# Motion_2.net
KiCad netlist of a schematic drawn in EAGLE
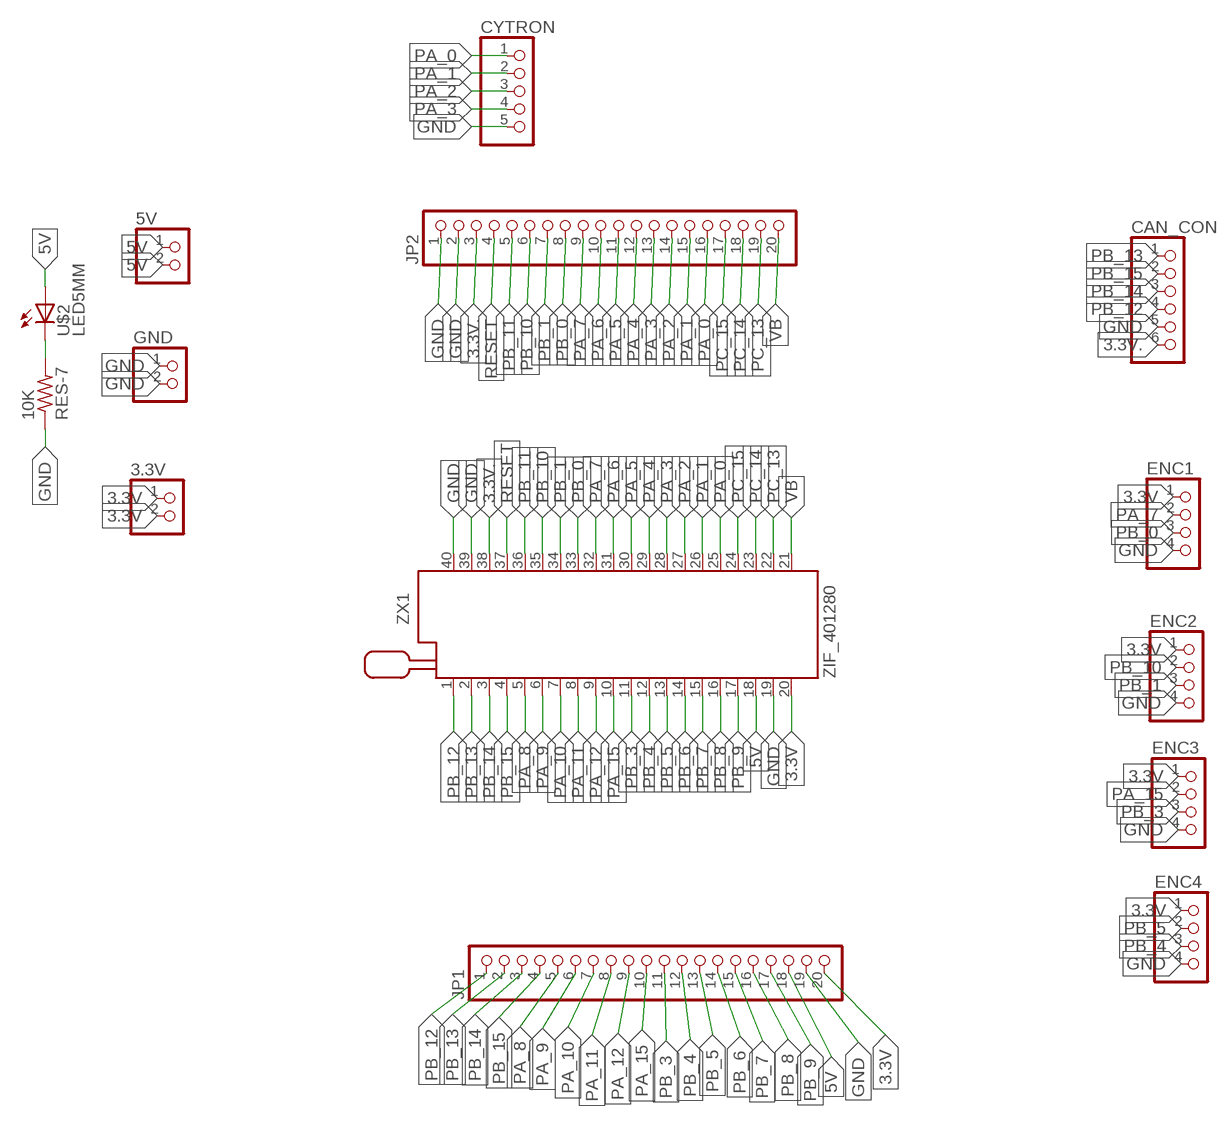
[diagram p0: schematic, sheet 1]

(export (version "E")
  (design (tool "Eeschema 10.0.6"))
  (components
    (comp (ref "3.3V")
      (value "PINHD-2_DATA")
      (footprint "eagle-import:1X02_DATA")
      (libsource (lib "eagle-import") (part "PINHD-2_DATA"))
    )
    (comp (ref "5V")
      (value "PINHD-2_DATA")
      (footprint "eagle-import:1X02_DATA")
      (libsource (lib "eagle-import") (part "PINHD-2_DATA"))
    )
    (comp (ref "10K")
      (value "RES-7")
      (footprint "eagle-import:0204_7")
      (libsource (lib "eagle-import") (part "RES-7"))
    )
    (comp (ref "CAN_CON")
      (value "PINHD-6_DATA")
      (footprint "eagle-import:1X06_DATA")
      (libsource (lib "eagle-import") (part "PINHD-6_DATA"))
    )
    (comp (ref "CYTRON")
      (value "PINHD-5_DATA")
      (footprint "eagle-import:1X05_DATA")
      (libsource (lib "eagle-import") (part "PINHD-5_DATA"))
    )
    (comp (ref "ENC1")
      (value "PINHD-4_DATA")
      (footprint "eagle-import:1X04_DATA")
      (libsource (lib "eagle-import") (part "PINHD-4_DATA"))
    )
    (comp (ref "ENC2")
      (value "PINHD-4_DATA")
      (footprint "eagle-import:1X04_DATA")
      (libsource (lib "eagle-import") (part "PINHD-4_DATA"))
    )
    (comp (ref "ENC3")
      (value "PINHD-4_DATA")
      (footprint "eagle-import:1X04_DATA")
      (libsource (lib "eagle-import") (part "PINHD-4_DATA"))
    )
    (comp (ref "ENC4")
      (value "PINHD-4_DATA")
      (footprint "eagle-import:1X04_DATA")
      (libsource (lib "eagle-import") (part "PINHD-4_DATA"))
    )
    (comp (ref "GND")
      (value "PINHD-2_DATA")
      (footprint "eagle-import:1X02_DATA")
      (libsource (lib "eagle-import") (part "PINHD-2_DATA"))
    )
    (comp (ref "JP1")
      (value "PINHD-1X20")
      (footprint "eagle-import:1X20")
      (libsource (lib "eagle-import") (part "PINHD-1X20"))
    )
    (comp (ref "JP2")
      (value "PINHD-1X20")
      (footprint "eagle-import:1X20")
      (libsource (lib "eagle-import") (part "PINHD-1X20"))
    )
    (comp (ref "U$2")
      (value "LED5MM")
      (footprint "eagle-import:LED5MM")
      (libsource (lib "eagle-import") (part "LED5MM"))
    )
    (comp (ref "ZX1")
      (value "ZIF_401280")
      (footprint "eagle-import:240-1280-00-0602J")
      (libsource (lib "eagle-import") (part "ZIF_401280"))
    )
  )
  (nets
    (net (code "1") (name "3.3V") (class "Default")
      (node (ref "3.3V") (pin "1") (pinfunction "1_1") (pintype "passive"))
      (node (ref "3.3V") (pin "2") (pinfunction "2_2") (pintype "passive"))
      (node (ref "ENC1") (pin "1") (pinfunction "1_1") (pintype "passive"))
      (node (ref "ENC2") (pin "1") (pinfunction "1_1") (pintype "passive"))
      (node (ref "ENC3") (pin "1") (pinfunction "1_1") (pintype "passive"))
      (node (ref "ENC4") (pin "1") (pinfunction "1_1") (pintype "passive"))
      (node (ref "JP1") (pin "20") (pinfunction "20_20") (pintype "passive"))
      (node (ref "ZX1") (pin "20") (pinfunction "20_20") (pintype "passive"))
    )
    (net (code "2") (name "3.3V.") (class "Default")
      (node (ref "CAN_CON") (pin "6") (pinfunction "6_6") (pintype "passive"))
      (node (ref "JP2") (pin "3") (pinfunction "3_3") (pintype "passive"))
      (node (ref "ZX1") (pin "38") (pinfunction "38_38") (pintype "passive"))
    )
    (net (code "3") (name "5V") (class "Default")
      (node (ref "5V") (pin "1") (pinfunction "1_1") (pintype "passive"))
      (node (ref "5V") (pin "2") (pinfunction "2_2") (pintype "passive"))
      (node (ref "JP1") (pin "18") (pinfunction "18_18") (pintype "passive"))
      (node (ref "U$2") (pin "A") (pinfunction "A_A") (pintype "passive"))
      (node (ref "ZX1") (pin "18") (pinfunction "18_18") (pintype "passive"))
    )
    (net (code "4") (name "GND") (class "Default")
      (node (ref "10K") (pin "1") (pinfunction "1_1") (pintype "passive"))
      (node (ref "CAN_CON") (pin "5") (pinfunction "5_5") (pintype "passive"))
      (node (ref "CYTRON") (pin "5") (pinfunction "5_5") (pintype "passive"))
      (node (ref "ENC1") (pin "4") (pinfunction "4_4") (pintype "passive"))
      (node (ref "ENC2") (pin "4") (pinfunction "4_4") (pintype "passive"))
      (node (ref "ENC3") (pin "4") (pinfunction "4_4") (pintype "passive"))
      (node (ref "ENC4") (pin "4") (pinfunction "4_4") (pintype "passive"))
      (node (ref "GND") (pin "1") (pinfunction "1_1") (pintype "passive"))
      (node (ref "GND") (pin "2") (pinfunction "2_2") (pintype "passive"))
      (node (ref "JP1") (pin "19") (pinfunction "19_19") (pintype "passive"))
      (node (ref "JP2") (pin "1") (pinfunction "1_1") (pintype "passive"))
      (node (ref "JP2") (pin "2") (pinfunction "2_2") (pintype "passive"))
      (node (ref "ZX1") (pin "19") (pinfunction "19_19") (pintype "passive"))
      (node (ref "ZX1") (pin "39") (pinfunction "39_39") (pintype "passive"))
      (node (ref "ZX1") (pin "40") (pinfunction "40_40") (pintype "passive"))
    )
    (net (code "5") (name "Net-(U$2-C)") (class "Default")
      (node (ref "10K") (pin "2") (pinfunction "2_2") (pintype "passive"))
      (node (ref "U$2") (pin "K") (pinfunction "C_K") (pintype "passive"))
    )
    (net (code "6") (name "PA_0") (class "Default")
      (node (ref "CYTRON") (pin "1") (pinfunction "1_1") (pintype "passive"))
      (node (ref "JP2") (pin "16") (pinfunction "16_16") (pintype "passive"))
      (node (ref "ZX1") (pin "25") (pinfunction "25_25") (pintype "passive"))
    )
    (net (code "7") (name "PA_1") (class "Default")
      (node (ref "CYTRON") (pin "2") (pinfunction "2_2") (pintype "passive"))
      (node (ref "JP2") (pin "15") (pinfunction "15_15") (pintype "passive"))
      (node (ref "ZX1") (pin "26") (pinfunction "26_26") (pintype "passive"))
    )
    (net (code "8") (name "PA_2") (class "Default")
      (node (ref "CYTRON") (pin "3") (pinfunction "3_3") (pintype "passive"))
      (node (ref "JP2") (pin "14") (pinfunction "14_14") (pintype "passive"))
      (node (ref "ZX1") (pin "27") (pinfunction "27_27") (pintype "passive"))
    )
    (net (code "9") (name "PA_3") (class "Default")
      (node (ref "CYTRON") (pin "4") (pinfunction "4_4") (pintype "passive"))
      (node (ref "JP2") (pin "13") (pinfunction "13_13") (pintype "passive"))
      (node (ref "ZX1") (pin "28") (pinfunction "28_28") (pintype "passive"))
    )
    (net (code "10") (name "PA_4") (class "Default")
      (node (ref "JP2") (pin "12") (pinfunction "12_12") (pintype "passive"))
      (node (ref "ZX1") (pin "29") (pinfunction "29_29") (pintype "passive"))
    )
    (net (code "11") (name "PA_5") (class "Default")
      (node (ref "JP2") (pin "11") (pinfunction "11_11") (pintype "passive"))
      (node (ref "ZX1") (pin "30") (pinfunction "30_30") (pintype "passive"))
    )
    (net (code "12") (name "PA_6") (class "Default")
      (node (ref "JP2") (pin "10") (pinfunction "10_10") (pintype "passive"))
      (node (ref "ZX1") (pin "31") (pinfunction "31_31") (pintype "passive"))
    )
    (net (code "13") (name "PA_7") (class "Default")
      (node (ref "ENC1") (pin "2") (pinfunction "2_2") (pintype "passive"))
      (node (ref "JP2") (pin "9") (pinfunction "9_9") (pintype "passive"))
      (node (ref "ZX1") (pin "32") (pinfunction "32_32") (pintype "passive"))
    )
    (net (code "14") (name "PA_8") (class "Default")
      (node (ref "JP1") (pin "5") (pinfunction "5_5") (pintype "passive"))
      (node (ref "ZX1") (pin "5") (pinfunction "5_5") (pintype "passive"))
    )
    (net (code "15") (name "PA_9") (class "Default")
      (node (ref "JP1") (pin "6") (pinfunction "6_6") (pintype "passive"))
      (node (ref "ZX1") (pin "6") (pinfunction "6_6") (pintype "passive"))
    )
    (net (code "16") (name "PA_10") (class "Default")
      (node (ref "JP1") (pin "7") (pinfunction "7_7") (pintype "passive"))
      (node (ref "ZX1") (pin "7") (pinfunction "7_7") (pintype "passive"))
    )
    (net (code "17") (name "PA_11") (class "Default")
      (node (ref "JP1") (pin "8") (pinfunction "8_8") (pintype "passive"))
      (node (ref "ZX1") (pin "8") (pinfunction "8_8") (pintype "passive"))
    )
    (net (code "18") (name "PA_12") (class "Default")
      (node (ref "JP1") (pin "9") (pinfunction "9_9") (pintype "passive"))
      (node (ref "ZX1") (pin "9") (pinfunction "9_9") (pintype "passive"))
    )
    (net (code "19") (name "PA_15") (class "Default")
      (node (ref "ENC3") (pin "2") (pinfunction "2_2") (pintype "passive"))
      (node (ref "JP1") (pin "10") (pinfunction "10_10") (pintype "passive"))
      (node (ref "ZX1") (pin "10") (pinfunction "10_10") (pintype "passive"))
    )
    (net (code "20") (name "PB_0") (class "Default")
      (node (ref "ENC1") (pin "3") (pinfunction "3_3") (pintype "passive"))
      (node (ref "JP2") (pin "8") (pinfunction "8_8") (pintype "passive"))
      (node (ref "ZX1") (pin "33") (pinfunction "33_33") (pintype "passive"))
    )
    (net (code "21") (name "PB_1") (class "Default")
      (node (ref "ENC2") (pin "3") (pinfunction "3_3") (pintype "passive"))
      (node (ref "JP2") (pin "7") (pinfunction "7_7") (pintype "passive"))
      (node (ref "ZX1") (pin "34") (pinfunction "34_34") (pintype "passive"))
    )
    (net (code "22") (name "PB_3") (class "Default")
      (node (ref "ENC3") (pin "3") (pinfunction "3_3") (pintype "passive"))
      (node (ref "JP1") (pin "11") (pinfunction "11_11") (pintype "passive"))
      (node (ref "ZX1") (pin "11") (pinfunction "11_11") (pintype "passive"))
    )
    (net (code "23") (name "PB_4") (class "Default")
      (node (ref "ENC4") (pin "3") (pinfunction "3_3") (pintype "passive"))
      (node (ref "JP1") (pin "12") (pinfunction "12_12") (pintype "passive"))
      (node (ref "ZX1") (pin "12") (pinfunction "12_12") (pintype "passive"))
    )
    (net (code "24") (name "PB_5") (class "Default")
      (node (ref "ENC4") (pin "2") (pinfunction "2_2") (pintype "passive"))
      (node (ref "JP1") (pin "13") (pinfunction "13_13") (pintype "passive"))
      (node (ref "ZX1") (pin "13") (pinfunction "13_13") (pintype "passive"))
    )
    (net (code "25") (name "PB_6") (class "Default")
      (node (ref "JP1") (pin "14") (pinfunction "14_14") (pintype "passive"))
      (node (ref "ZX1") (pin "14") (pinfunction "14_14") (pintype "passive"))
    )
    (net (code "26") (name "PB_7") (class "Default")
      (node (ref "JP1") (pin "15") (pinfunction "15_15") (pintype "passive"))
      (node (ref "ZX1") (pin "15") (pinfunction "15_15") (pintype "passive"))
    )
    (net (code "27") (name "PB_8") (class "Default")
      (node (ref "JP1") (pin "16") (pinfunction "16_16") (pintype "passive"))
      (node (ref "ZX1") (pin "16") (pinfunction "16_16") (pintype "passive"))
    )
    (net (code "28") (name "PB_9") (class "Default")
      (node (ref "JP1") (pin "17") (pinfunction "17_17") (pintype "passive"))
      (node (ref "ZX1") (pin "17") (pinfunction "17_17") (pintype "passive"))
    )
    (net (code "29") (name "PB_10") (class "Default")
      (node (ref "ENC2") (pin "2") (pinfunction "2_2") (pintype "passive"))
      (node (ref "JP2") (pin "6") (pinfunction "6_6") (pintype "passive"))
      (node (ref "ZX1") (pin "35") (pinfunction "35_35") (pintype "passive"))
    )
    (net (code "30") (name "PB_11") (class "Default")
      (node (ref "JP2") (pin "5") (pinfunction "5_5") (pintype "passive"))
      (node (ref "ZX1") (pin "36") (pinfunction "36_36") (pintype "passive"))
    )
    (net (code "31") (name "PB_12") (class "Default")
      (node (ref "CAN_CON") (pin "4") (pinfunction "4_4") (pintype "passive"))
      (node (ref "JP1") (pin "1") (pinfunction "1_1") (pintype "passive"))
      (node (ref "ZX1") (pin "1") (pinfunction "1_1") (pintype "passive"))
    )
    (net (code "32") (name "PB_13") (class "Default")
      (node (ref "CAN_CON") (pin "1") (pinfunction "1_1") (pintype "passive"))
      (node (ref "JP1") (pin "2") (pinfunction "2_2") (pintype "passive"))
      (node (ref "ZX1") (pin "2") (pinfunction "2_2") (pintype "passive"))
    )
    (net (code "33") (name "PB_14") (class "Default")
      (node (ref "CAN_CON") (pin "3") (pinfunction "3_3") (pintype "passive"))
      (node (ref "JP1") (pin "3") (pinfunction "3_3") (pintype "passive"))
      (node (ref "ZX1") (pin "3") (pinfunction "3_3") (pintype "passive"))
    )
    (net (code "34") (name "PB_15") (class "Default")
      (node (ref "CAN_CON") (pin "2") (pinfunction "2_2") (pintype "passive"))
      (node (ref "JP1") (pin "4") (pinfunction "4_4") (pintype "passive"))
      (node (ref "ZX1") (pin "4") (pinfunction "4_4") (pintype "passive"))
    )
    (net (code "35") (name "PC_13") (class "Default")
      (node (ref "JP2") (pin "19") (pinfunction "19_19") (pintype "passive"))
      (node (ref "ZX1") (pin "22") (pinfunction "22_22") (pintype "passive"))
    )
    (net (code "36") (name "PC_14") (class "Default")
      (node (ref "JP2") (pin "18") (pinfunction "18_18") (pintype "passive"))
      (node (ref "ZX1") (pin "23") (pinfunction "23_23") (pintype "passive"))
    )
    (net (code "37") (name "PC_15") (class "Default")
      (node (ref "JP2") (pin "17") (pinfunction "17_17") (pintype "passive"))
      (node (ref "ZX1") (pin "24") (pinfunction "24_24") (pintype "passive"))
    )
    (net (code "38") (name "RESET") (class "Default")
      (node (ref "JP2") (pin "4") (pinfunction "4_4") (pintype "passive"))
      (node (ref "ZX1") (pin "37") (pinfunction "37_37") (pintype "passive"))
    )
    (net (code "39") (name "VB") (class "Default")
      (node (ref "JP2") (pin "20") (pinfunction "20_20") (pintype "passive"))
      (node (ref "ZX1") (pin "21") (pinfunction "21_21") (pintype "passive"))
    )
  )
)
